# HUB.net
KiCad netlist of a schematic drawn in Altium Designer
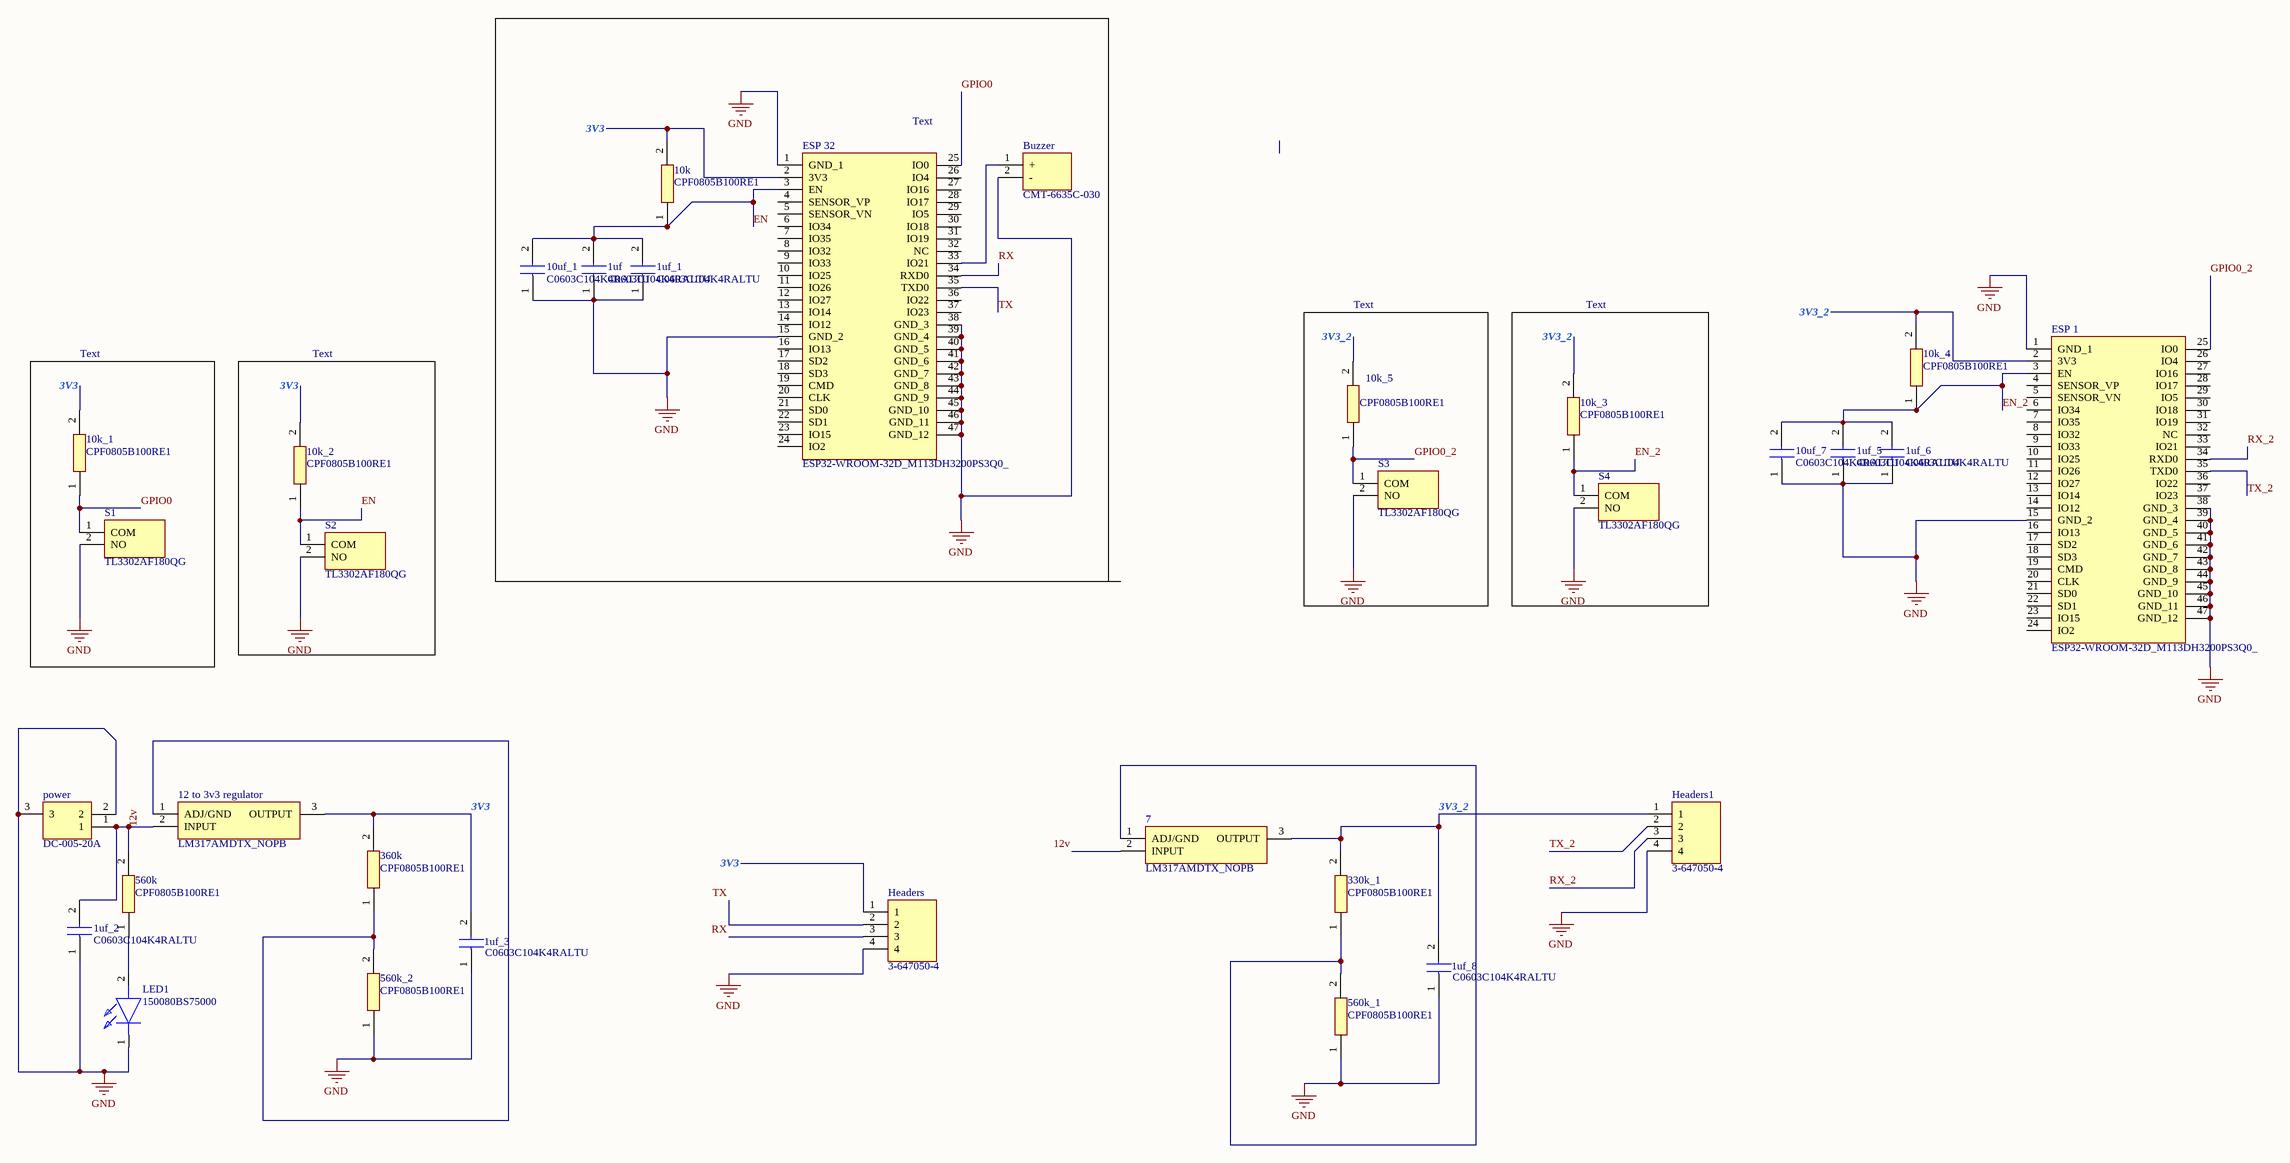
[diagram p0: HUB.SchDoc]

(export (version "E")
  (design (tool "Eeschema 10.0.6"))
  (components
    (comp (ref "1uf")
      (value "C0603C104K4RALTU")
      (footprint "SamacSys:C0603")
      (description "Capacitor")
      (fields (field (name "MOUSER PART NUMBER") "80-C0603C104K4RAL"))
      (libsource (lib "*") (part "C0603C104K4RALTU"))
    )
    (comp (ref "1uf_1")
      (value "C0603C104K4RALTU")
      (footprint "SamacSys:C0603")
      (description "Capacitor")
      (fields (field (name "MOUSER PART NUMBER") "80-C0603C104K4RAL"))
      (libsource (lib "*") (part "C0603C104K4RALTU"))
    )
    (comp (ref "1uf_2")
      (value "C0603C104K4RALTU")
      (footprint "SamacSys:C0603")
      (description "Capacitor")
      (fields (field (name "MOUSER PART NUMBER") "80-C0603C104K4RAL"))
      (libsource (lib "*") (part "C0603C104K4RALTU"))
    )
    (comp (ref "1uf_3")
      (value "C0603C104K4RALTU")
      (footprint "SamacSys:C0603")
      (description "Capacitor")
      (fields (field (name "MOUSER PART NUMBER") "80-C0603C104K4RAL"))
      (libsource (lib "*") (part "C0603C104K4RALTU"))
    )
    (comp (ref "1uf_5")
      (value "C0603C104K4RALTU")
      (footprint "SamacSys:C0603")
      (description "Capacitor")
      (fields (field (name "MOUSER PART NUMBER") "80-C0603C104K4RAL"))
      (libsource (lib "*") (part "C0603C104K4RALTU"))
    )
    (comp (ref "1uf_6")
      (value "C0603C104K4RALTU")
      (footprint "SamacSys:C0603")
      (description "Capacitor")
      (fields (field (name "MOUSER PART NUMBER") "80-C0603C104K4RAL"))
      (libsource (lib "*") (part "C0603C104K4RALTU"))
    )
    (comp (ref "1uf_8")
      (value "C0603C104K4RALTU")
      (footprint "SamacSys:C0603")
      (description "Capacitor")
      (fields (field (name "MOUSER PART NUMBER") "80-C0603C104K4RAL"))
      (libsource (lib "*") (part "C0603C104K4RALTU"))
    )
    (comp (ref "7")
      (value "LM317AMDTX_NOPB")
      (footprint "SamacSys:LM78M05CDT")
      (description "Integrated Circuit")
      (fields
        (field (name "MANUFACTURER_PART_NUMBER") "LM317AMDTX/NOPB")
        (field (name "MOUSER PART NUMBER") "926-LM317AMDTX/NOPB")
      )
      (libsource (lib "*") (part "LM317AMDTX_NOPB"))
    )
    (comp (ref "10k")
      (value "CPF0805B100RE1")
      (footprint "SamacSys:RESC2012X65N")
      (description "Resistor")
      (fields (field (name "MOUSER PART NUMBER") "279-CPF0805B100RE1"))
      (libsource (lib "*") (part "CPF0805B100RE1"))
    )
    (comp (ref "10k_1")
      (value "CPF0805B100RE1")
      (footprint "SamacSys:RESC2012X65N")
      (description "Resistor")
      (fields (field (name "MOUSER PART NUMBER") "279-CPF0805B100RE1"))
      (libsource (lib "*") (part "CPF0805B100RE1"))
    )
    (comp (ref "10k_2")
      (value "CPF0805B100RE1")
      (footprint "SamacSys:RESC2012X65N")
      (description "Resistor")
      (fields (field (name "MOUSER PART NUMBER") "279-CPF0805B100RE1"))
      (libsource (lib "*") (part "CPF0805B100RE1"))
    )
    (comp (ref "10k_3")
      (value "CPF0805B100RE1")
      (footprint "SamacSys:RESC2012X65N")
      (description "Resistor")
      (fields (field (name "MOUSER PART NUMBER") "279-CPF0805B100RE1"))
      (libsource (lib "*") (part "CPF0805B100RE1"))
    )
    (comp (ref "10k_4")
      (value "CPF0805B100RE1")
      (footprint "SamacSys:RESC2012X65N")
      (description "Resistor")
      (fields (field (name "MOUSER PART NUMBER") "279-CPF0805B100RE1"))
      (libsource (lib "*") (part "CPF0805B100RE1"))
    )
    (comp (ref "10k_5")
      (value "CPF0805B100RE1")
      (footprint "SamacSys:RESC2012X65N")
      (description "Resistor")
      (fields (field (name "MOUSER PART NUMBER") "279-CPF0805B100RE1"))
      (libsource (lib "*") (part "CPF0805B100RE1"))
    )
    (comp (ref "10uf_1")
      (value "C0603C104K4RALTU")
      (footprint "SamacSys:C0603")
      (description "Capacitor")
      (fields (field (name "MOUSER PART NUMBER") "80-C0603C104K4RAL"))
      (libsource (lib "*") (part "C0603C104K4RALTU"))
    )
    (comp (ref "10uf_7")
      (value "C0603C104K4RALTU")
      (footprint "SamacSys:C0603")
      (description "Capacitor")
      (fields (field (name "MOUSER PART NUMBER") "80-C0603C104K4RAL"))
      (libsource (lib "*") (part "C0603C104K4RALTU"))
    )
    (comp (ref "12 to 3v3 regulator")
      (value "LM317AMDTX_NOPB")
      (footprint "SamacSys:LM78M05CDT")
      (description "Integrated Circuit")
      (fields
        (field (name "MANUFACTURER_PART_NUMBER") "LM317AMDTX/NOPB")
        (field (name "MOUSER PART NUMBER") "926-LM317AMDTX/NOPB")
      )
      (libsource (lib "*") (part "LM317AMDTX_NOPB"))
    )
    (comp (ref "330k_1")
      (value "CPF0805B100RE1")
      (footprint "SamacSys:RESC2012X65N")
      (description "Resistor")
      (fields (field (name "MOUSER PART NUMBER") "279-CPF0805B100RE1"))
      (libsource (lib "*") (part "CPF0805B100RE1"))
    )
    (comp (ref "360k")
      (value "CPF0805B100RE1")
      (footprint "SamacSys:RESC2012X65N")
      (description "Resistor")
      (fields (field (name "MOUSER PART NUMBER") "279-CPF0805B100RE1"))
      (libsource (lib "*") (part "CPF0805B100RE1"))
    )
    (comp (ref "560k")
      (value "CPF0805B100RE1")
      (footprint "SamacSys:RESC2012X65N")
      (description "Resistor")
      (fields (field (name "MOUSER PART NUMBER") "279-CPF0805B100RE1"))
      (libsource (lib "*") (part "CPF0805B100RE1"))
    )
    (comp (ref "560k_1")
      (value "CPF0805B100RE1")
      (footprint "SamacSys:RESC2012X65N")
      (description "Resistor")
      (fields (field (name "MOUSER PART NUMBER") "279-CPF0805B100RE1"))
      (libsource (lib "*") (part "CPF0805B100RE1"))
    )
    (comp (ref "560k_2")
      (value "CPF0805B100RE1")
      (footprint "SamacSys:RESC2012X65N")
      (description "Resistor")
      (fields (field (name "MOUSER PART NUMBER") "279-CPF0805B100RE1"))
      (libsource (lib "*") (part "CPF0805B100RE1"))
    )
    (comp (ref "Buzzer")
      (value "CMT-6635C-030")
      (footprint "SamacSys:CMT6635C030")
      (description "Undefined or Miscellaneous")
      (fields (field (name "MOUSER PART NUMBER") "490-CMT-6635C-030"))
      (libsource (lib "*") (part "CMT-6635C-030"))
    )
    (comp (ref "ESP 1")
      (value "ESP32-WROOM-32D_M113DH3200PS3Q0_")
      (footprint "SamacSys:ESP32WROOM32DM113DH3200PS3Q0")
      (description "Integrated Circuit")
      (fields
        (field (name "MANUFACTURER_PART_NUMBER") "ESP32-WROOM-32D(M113DH3200PS3Q0)")
        (field (name "MOUSER PART NUMBER") "356-ESPWROOM3200PS3")
      )
      (libsource (lib "*") (part "ESP32-WROOM-32D_M113DH3200PS3Q0_"))
    )
    (comp (ref "ESP 32")
      (value "ESP32-WROOM-32D_M113DH3200PS3Q0_")
      (footprint "SamacSys:ESP32WROOM32DM113DH3200PS3Q0")
      (description "Integrated Circuit")
      (fields
        (field (name "MANUFACTURER_PART_NUMBER") "ESP32-WROOM-32D(M113DH3200PS3Q0)")
        (field (name "MOUSER PART NUMBER") "356-ESPWROOM3200PS3")
      )
      (libsource (lib "*") (part "ESP32-WROOM-32D_M113DH3200PS3Q0_"))
    )
    (comp (ref "Headers")
      (value "3-647050-4")
      (footprint "SamacSys:SHDR4W66P0X254_1X4_1016X635X1079P")
      (description "Connector")
      (fields (field (name "MOUSER PART NUMBER") "571-3-647050-4"))
      (libsource (lib "*") (part "3-647050-4"))
    )
    (comp (ref "Headers1")
      (value "3-647050-4")
      (footprint "SamacSys:SHDR4W66P0X254_1X4_1016X635X1079P")
      (description "Connector")
      (fields (field (name "MOUSER PART NUMBER") "571-3-647050-4"))
      (libsource (lib "*") (part "3-647050-4"))
    )
    (comp (ref "LED1")
      (value "150080BS75000")
      (footprint "SamacSys:LEDC2012X80N")
      (description "LED")
      (fields (field (name "MOUSER PART NUMBER") "710-150080BS75000"))
      (libsource (lib "*") (part "150080BS75000"))
    )
    (comp (ref "power")
      (value "DC-005-20A")
      (footprint "SamacSys:DC00520A")
      (description "Connector")
      (libsource (lib "*") (part "DC-005-20A"))
    )
    (comp (ref "S1")
      (value "TL3302AF180QG")
      (footprint "SamacSys:TL3302AF180QG")
      (description "Switch")
      (fields (field (name "MOUSER PART NUMBER") "612-TL3302A"))
      (libsource (lib "*") (part "TL3302AF180QG"))
    )
    (comp (ref "S2")
      (value "TL3302AF180QG")
      (footprint "SamacSys:TL3302AF180QG")
      (description "Switch")
      (fields (field (name "MOUSER PART NUMBER") "612-TL3302A"))
      (libsource (lib "*") (part "TL3302AF180QG"))
    )
    (comp (ref "S3")
      (value "TL3302AF180QG")
      (footprint "SamacSys:TL3302AF180QG")
      (description "Switch")
      (fields (field (name "MOUSER PART NUMBER") "612-TL3302A"))
      (libsource (lib "*") (part "TL3302AF180QG"))
    )
    (comp (ref "S4")
      (value "TL3302AF180QG")
      (footprint "SamacSys:TL3302AF180QG")
      (description "Switch")
      (fields (field (name "MOUSER PART NUMBER") "612-TL3302A"))
      (libsource (lib "*") (part "TL3302AF180QG"))
    )
  )
  (nets
    (net (code "1") (name "/3V3") (class "Default")
      (node (ref "10k") (pin "2") (pinfunction "2_2") (pintype "passive"))
      (node (ref "10k_1") (pin "2") (pinfunction "2_2") (pintype "passive"))
      (node (ref "10k_2") (pin "2") (pinfunction "2_2") (pintype "passive"))
      (node (ref "12 to 3v3 regulator") (pin "3") (pinfunction "OUTPUT_3") (pintype "passive"))
      (node (ref "1uf_3") (pin "2") (pinfunction "2_2") (pintype "passive"))
      (node (ref "360k") (pin "2") (pinfunction "2_2") (pintype "passive"))
      (node (ref "ESP 32") (pin "2") (pinfunction "3V3_2") (pintype "passive"))
      (node (ref "Headers") (pin "1") (pinfunction "1_1") (pintype "passive"))
    )
    (net (code "2") (name "/3V3_2") (class "Default")
      (node (ref "10k_3") (pin "2") (pinfunction "2_2") (pintype "passive"))
      (node (ref "10k_4") (pin "2") (pinfunction "2_2") (pintype "passive"))
      (node (ref "10k_5") (pin "2") (pinfunction "2_2") (pintype "passive"))
      (node (ref "1uf_8") (pin "2") (pinfunction "2_2") (pintype "passive"))
      (node (ref "330k_1") (pin "2") (pinfunction "2_2") (pintype "passive"))
      (node (ref "7") (pin "3") (pinfunction "OUTPUT_3") (pintype "passive"))
      (node (ref "ESP 1") (pin "2") (pinfunction "3V3_2") (pintype "passive"))
      (node (ref "Headers1") (pin "1") (pinfunction "1_1") (pintype "passive"))
    )
    (net (code "3") (name "/12v") (class "Default")
      (node (ref "12 to 3v3 regulator") (pin "2") (pinfunction "INPUT_2") (pintype "passive"))
      (node (ref "1uf_2") (pin "2") (pinfunction "2_2") (pintype "passive"))
      (node (ref "560k") (pin "2") (pinfunction "2_2") (pintype "passive"))
      (node (ref "7") (pin "2") (pinfunction "INPUT_2") (pintype "passive"))
      (node (ref "power") (pin "1") (pinfunction "1_1") (pintype "passive"))
    )
    (net (code "4") (name "/EN") (class "Default")
      (node (ref "10k") (pin "1") (pinfunction "1_1") (pintype "passive"))
      (node (ref "10k_2") (pin "1") (pinfunction "1_1") (pintype "passive"))
      (node (ref "10uf_1") (pin "2") (pinfunction "2_2") (pintype "passive"))
      (node (ref "1uf") (pin "2") (pinfunction "2_2") (pintype "passive"))
      (node (ref "1uf_1") (pin "2") (pinfunction "2_2") (pintype "passive"))
      (node (ref "ESP 32") (pin "3") (pinfunction "EN_3") (pintype "passive"))
      (node (ref "S2") (pin "1") (pinfunction "COM_1") (pintype "passive"))
    )
    (net (code "5") (name "/EN_2") (class "Default")
      (node (ref "10k_3") (pin "1") (pinfunction "1_1") (pintype "passive"))
      (node (ref "10k_4") (pin "1") (pinfunction "1_1") (pintype "passive"))
      (node (ref "10uf_7") (pin "2") (pinfunction "2_2") (pintype "passive"))
      (node (ref "1uf_5") (pin "2") (pinfunction "2_2") (pintype "passive"))
      (node (ref "1uf_6") (pin "2") (pinfunction "2_2") (pintype "passive"))
      (node (ref "ESP 1") (pin "3") (pinfunction "EN_3") (pintype "passive"))
      (node (ref "S4") (pin "1") (pinfunction "COM_1") (pintype "passive"))
    )
    (net (code "6") (name "/GPIO0") (class "Default")
      (node (ref "10k_1") (pin "1") (pinfunction "1_1") (pintype "passive"))
      (node (ref "ESP 32") (pin "25") (pinfunction "IO0_25") (pintype "passive"))
      (node (ref "S1") (pin "1") (pinfunction "COM_1") (pintype "passive"))
    )
    (net (code "7") (name "/GPIO0_2") (class "Default")
      (node (ref "10k_5") (pin "1") (pinfunction "1_1") (pintype "passive"))
      (node (ref "ESP 1") (pin "25") (pinfunction "IO0_25") (pintype "passive"))
      (node (ref "S3") (pin "1") (pinfunction "COM_1") (pintype "passive"))
    )
    (net (code "8") (name "/RX") (class "Default")
      (node (ref "ESP 32") (pin "34") (pinfunction "RXD0_34") (pintype "passive"))
      (node (ref "Headers") (pin "3") (pinfunction "3_3") (pintype "passive"))
    )
    (net (code "9") (name "/RX_2") (class "Default")
      (node (ref "ESP 1") (pin "34") (pinfunction "RXD0_34") (pintype "passive"))
      (node (ref "Headers1") (pin "3") (pinfunction "3_3") (pintype "passive"))
    )
    (net (code "10") (name "/TX") (class "Default")
      (node (ref "ESP 32") (pin "35") (pinfunction "TXD0_35") (pintype "passive"))
      (node (ref "Headers") (pin "2") (pinfunction "2_2") (pintype "passive"))
    )
    (net (code "11") (name "/TX_2") (class "Default")
      (node (ref "ESP 1") (pin "35") (pinfunction "TXD0_35") (pintype "passive"))
      (node (ref "Headers1") (pin "2") (pinfunction "2_2") (pintype "passive"))
    )
    (net (code "12") (name "GND") (class "Default")
      (node (ref "10uf_1") (pin "1") (pinfunction "1_1") (pintype "passive"))
      (node (ref "10uf_7") (pin "1") (pinfunction "1_1") (pintype "passive"))
      (node (ref "1uf") (pin "1") (pinfunction "1_1") (pintype "passive"))
      (node (ref "1uf_1") (pin "1") (pinfunction "1_1") (pintype "passive"))
      (node (ref "1uf_2") (pin "1") (pinfunction "1_1") (pintype "passive"))
      (node (ref "1uf_3") (pin "1") (pinfunction "1_1") (pintype "passive"))
      (node (ref "1uf_5") (pin "1") (pinfunction "1_1") (pintype "passive"))
      (node (ref "1uf_6") (pin "1") (pinfunction "1_1") (pintype "passive"))
      (node (ref "1uf_8") (pin "1") (pinfunction "1_1") (pintype "passive"))
      (node (ref "560k_1") (pin "1") (pinfunction "1_1") (pintype "passive"))
      (node (ref "560k_2") (pin "1") (pinfunction "1_1") (pintype "passive"))
      (node (ref "Buzzer") (pin "2") (pinfunction "-_2") (pintype "passive"))
      (node (ref "ESP 1") (pin "1") (pinfunction "GND_1_1") (pintype "passive"))
      (node (ref "ESP 1") (pin "15") (pinfunction "GND_2_15") (pintype "passive"))
      (node (ref "ESP 1") (pin "38") (pinfunction "GND_3_38") (pintype "passive"))
      (node (ref "ESP 1") (pin "39") (pinfunction "GND_4_39") (pintype "passive"))
      (node (ref "ESP 1") (pin "40") (pinfunction "GND_5_40") (pintype "passive"))
      (node (ref "ESP 1") (pin "41") (pinfunction "GND_6_41") (pintype "passive"))
      (node (ref "ESP 1") (pin "42") (pinfunction "GND_7_42") (pintype "passive"))
      (node (ref "ESP 1") (pin "43") (pinfunction "GND_8_43") (pintype "passive"))
      (node (ref "ESP 1") (pin "44") (pinfunction "GND_9_44") (pintype "passive"))
      (node (ref "ESP 1") (pin "45") (pinfunction "GND_10_45") (pintype "passive"))
      (node (ref "ESP 1") (pin "46") (pinfunction "GND_11_46") (pintype "passive"))
      (node (ref "ESP 1") (pin "47") (pinfunction "GND_12_47") (pintype "passive"))
      (node (ref "ESP 32") (pin "1") (pinfunction "GND_1_1") (pintype "passive"))
      (node (ref "ESP 32") (pin "15") (pinfunction "GND_2_15") (pintype "passive"))
      (node (ref "ESP 32") (pin "38") (pinfunction "GND_3_38") (pintype "passive"))
      (node (ref "ESP 32") (pin "39") (pinfunction "GND_4_39") (pintype "passive"))
      (node (ref "ESP 32") (pin "40") (pinfunction "GND_5_40") (pintype "passive"))
      (node (ref "ESP 32") (pin "41") (pinfunction "GND_6_41") (pintype "passive"))
      (node (ref "ESP 32") (pin "42") (pinfunction "GND_7_42") (pintype "passive"))
      (node (ref "ESP 32") (pin "43") (pinfunction "GND_8_43") (pintype "passive"))
      (node (ref "ESP 32") (pin "44") (pinfunction "GND_9_44") (pintype "passive"))
      (node (ref "ESP 32") (pin "45") (pinfunction "GND_10_45") (pintype "passive"))
      (node (ref "ESP 32") (pin "46") (pinfunction "GND_11_46") (pintype "passive"))
      (node (ref "ESP 32") (pin "47") (pinfunction "GND_12_47") (pintype "passive"))
      (node (ref "Headers") (pin "4") (pinfunction "4_4") (pintype "passive"))
      (node (ref "Headers1") (pin "4") (pinfunction "4_4") (pintype "passive"))
      (node (ref "LED1") (pin "1") (pinfunction "K_1") (pintype "passive"))
      (node (ref "S1") (pin "2") (pinfunction "NO_2") (pintype "passive"))
      (node (ref "S2") (pin "2") (pinfunction "NO_2") (pintype "passive"))
      (node (ref "S3") (pin "2") (pinfunction "NO_2") (pintype "passive"))
      (node (ref "S4") (pin "2") (pinfunction "NO_2") (pintype "passive"))
      (node (ref "power") (pin "2") (pinfunction "2_2") (pintype "passive"))
      (node (ref "power") (pin "3") (pinfunction "3_3") (pintype "passive"))
    )
    (net (code "13") (name "Net-(7-ADJ{slash}GND)") (class "Default")
      (node (ref "330k_1") (pin "1") (pinfunction "1_1") (pintype "passive"))
      (node (ref "560k_1") (pin "2") (pinfunction "2_2") (pintype "passive"))
      (node (ref "7") (pin "1") (pinfunction "ADJ/GND_1") (pintype "passive"))
    )
    (net (code "14") (name "Net-(12 to 3v3 regulator-ADJ{slash}GND)") (class "Default")
      (node (ref "12 to 3v3 regulator") (pin "1") (pinfunction "ADJ/GND_1") (pintype "passive"))
      (node (ref "360k") (pin "1") (pinfunction "1_1") (pintype "passive"))
      (node (ref "560k_2") (pin "2") (pinfunction "2_2") (pintype "passive"))
    )
    (net (code "15") (name "Net-(Buzzer-+)") (class "Default")
      (node (ref "Buzzer") (pin "1") (pinfunction "+_1") (pintype "passive"))
      (node (ref "ESP 32") (pin "33") (pinfunction "IO21_33") (pintype "passive"))
    )
    (net (code "16") (name "Net-(LED1-A)") (class "Default")
      (node (ref "560k") (pin "1") (pinfunction "1_1") (pintype "passive"))
      (node (ref "LED1") (pin "2") (pinfunction "A_2") (pintype "passive"))
    )
    (net (code "17") (name "unconnected-(ESP 1-CLK-Pad20)") (class "Default")
      (node (ref "ESP 1") (pin "20") (pinfunction "CLK_20") (pintype "passive"))
    )
    (net (code "18") (name "unconnected-(ESP 1-CMD-Pad19)") (class "Default")
      (node (ref "ESP 1") (pin "19") (pinfunction "CMD_19") (pintype "passive"))
    )
    (net (code "19") (name "unconnected-(ESP 1-IO2-Pad24)") (class "Default")
      (node (ref "ESP 1") (pin "24") (pinfunction "IO2_24") (pintype "passive"))
    )
    (net (code "20") (name "unconnected-(ESP 1-IO4-Pad26)") (class "Default")
      (node (ref "ESP 1") (pin "26") (pinfunction "IO4_26") (pintype "passive"))
    )
    (net (code "21") (name "unconnected-(ESP 1-IO5-Pad29)") (class "Default")
      (node (ref "ESP 1") (pin "29") (pinfunction "IO5_29") (pintype "passive"))
    )
    (net (code "22") (name "unconnected-(ESP 1-IO12-Pad14)") (class "Default")
      (node (ref "ESP 1") (pin "14") (pinfunction "IO12_14") (pintype "passive"))
    )
    (net (code "23") (name "unconnected-(ESP 1-IO13-Pad16)") (class "Default")
      (node (ref "ESP 1") (pin "16") (pinfunction "IO13_16") (pintype "passive"))
    )
    (net (code "24") (name "unconnected-(ESP 1-IO14-Pad13)") (class "Default")
      (node (ref "ESP 1") (pin "13") (pinfunction "IO14_13") (pintype "passive"))
    )
    (net (code "25") (name "unconnected-(ESP 1-IO15-Pad23)") (class "Default")
      (node (ref "ESP 1") (pin "23") (pinfunction "IO15_23") (pintype "passive"))
    )
    (net (code "26") (name "unconnected-(ESP 1-IO16-Pad27)") (class "Default")
      (node (ref "ESP 1") (pin "27") (pinfunction "IO16_27") (pintype "passive"))
    )
    (net (code "27") (name "unconnected-(ESP 1-IO17-Pad28)") (class "Default")
      (node (ref "ESP 1") (pin "28") (pinfunction "IO17_28") (pintype "passive"))
    )
    (net (code "28") (name "unconnected-(ESP 1-IO18-Pad30)") (class "Default")
      (node (ref "ESP 1") (pin "30") (pinfunction "IO18_30") (pintype "passive"))
    )
    (net (code "29") (name "unconnected-(ESP 1-IO19-Pad31)") (class "Default")
      (node (ref "ESP 1") (pin "31") (pinfunction "IO19_31") (pintype "passive"))
    )
    (net (code "30") (name "unconnected-(ESP 1-IO21-Pad33)") (class "Default")
      (node (ref "ESP 1") (pin "33") (pinfunction "IO21_33") (pintype "passive"))
    )
    (net (code "31") (name "unconnected-(ESP 1-IO22-Pad36)") (class "Default")
      (node (ref "ESP 1") (pin "36") (pinfunction "IO22_36") (pintype "passive"))
    )
    (net (code "32") (name "unconnected-(ESP 1-IO23-Pad37)") (class "Default")
      (node (ref "ESP 1") (pin "37") (pinfunction "IO23_37") (pintype "passive"))
    )
    (net (code "33") (name "unconnected-(ESP 1-IO25-Pad10)") (class "Default")
      (node (ref "ESP 1") (pin "10") (pinfunction "IO25_10") (pintype "passive"))
    )
    (net (code "34") (name "unconnected-(ESP 1-IO26-Pad11)") (class "Default")
      (node (ref "ESP 1") (pin "11") (pinfunction "IO26_11") (pintype "passive"))
    )
    (net (code "35") (name "unconnected-(ESP 1-IO27-Pad12)") (class "Default")
      (node (ref "ESP 1") (pin "12") (pinfunction "IO27_12") (pintype "passive"))
    )
    (net (code "36") (name "unconnected-(ESP 1-IO32-Pad8)") (class "Default")
      (node (ref "ESP 1") (pin "8") (pinfunction "IO32_8") (pintype "passive"))
    )
    (net (code "37") (name "unconnected-(ESP 1-IO33-Pad9)") (class "Default")
      (node (ref "ESP 1") (pin "9") (pinfunction "IO33_9") (pintype "passive"))
    )
    (net (code "38") (name "unconnected-(ESP 1-IO34-Pad6)") (class "Default")
      (node (ref "ESP 1") (pin "6") (pinfunction "IO34_6") (pintype "passive"))
    )
    (net (code "39") (name "unconnected-(ESP 1-IO35-Pad7)") (class "Default")
      (node (ref "ESP 1") (pin "7") (pinfunction "IO35_7") (pintype "passive"))
    )
    (net (code "40") (name "unconnected-(ESP 1-NC-Pad32)") (class "Default")
      (node (ref "ESP 1") (pin "32") (pinfunction "NC_32") (pintype "passive"))
    )
    (net (code "41") (name "unconnected-(ESP 1-SD0-Pad21)") (class "Default")
      (node (ref "ESP 1") (pin "21") (pinfunction "SD0_21") (pintype "passive"))
    )
    (net (code "42") (name "unconnected-(ESP 1-SD1-Pad22)") (class "Default")
      (node (ref "ESP 1") (pin "22") (pinfunction "SD1_22") (pintype "passive"))
    )
    (net (code "43") (name "unconnected-(ESP 1-SD2-Pad17)") (class "Default")
      (node (ref "ESP 1") (pin "17") (pinfunction "SD2_17") (pintype "passive"))
    )
    (net (code "44") (name "unconnected-(ESP 1-SD3-Pad18)") (class "Default")
      (node (ref "ESP 1") (pin "18") (pinfunction "SD3_18") (pintype "passive"))
    )
    (net (code "45") (name "unconnected-(ESP 1-SENSOR_VN-Pad5)") (class "Default")
      (node (ref "ESP 1") (pin "5") (pinfunction "SENSOR_VN_5") (pintype "passive"))
    )
    (net (code "46") (name "unconnected-(ESP 1-SENSOR_VP-Pad4)") (class "Default")
      (node (ref "ESP 1") (pin "4") (pinfunction "SENSOR_VP_4") (pintype "passive"))
    )
    (net (code "47") (name "unconnected-(ESP 32-CLK-Pad20)") (class "Default")
      (node (ref "ESP 32") (pin "20") (pinfunction "CLK_20") (pintype "passive"))
    )
    (net (code "48") (name "unconnected-(ESP 32-CMD-Pad19)") (class "Default")
      (node (ref "ESP 32") (pin "19") (pinfunction "CMD_19") (pintype "passive"))
    )
    (net (code "49") (name "unconnected-(ESP 32-IO2-Pad24)") (class "Default")
      (node (ref "ESP 32") (pin "24") (pinfunction "IO2_24") (pintype "passive"))
    )
    (net (code "50") (name "unconnected-(ESP 32-IO4-Pad26)") (class "Default")
      (node (ref "ESP 32") (pin "26") (pinfunction "IO4_26") (pintype "passive"))
    )
    (net (code "51") (name "unconnected-(ESP 32-IO5-Pad29)") (class "Default")
      (node (ref "ESP 32") (pin "29") (pinfunction "IO5_29") (pintype "passive"))
    )
    (net (code "52") (name "unconnected-(ESP 32-IO12-Pad14)") (class "Default")
      (node (ref "ESP 32") (pin "14") (pinfunction "IO12_14") (pintype "passive"))
    )
    (net (code "53") (name "unconnected-(ESP 32-IO13-Pad16)") (class "Default")
      (node (ref "ESP 32") (pin "16") (pinfunction "IO13_16") (pintype "passive"))
    )
    (net (code "54") (name "unconnected-(ESP 32-IO14-Pad13)") (class "Default")
      (node (ref "ESP 32") (pin "13") (pinfunction "IO14_13") (pintype "passive"))
    )
    (net (code "55") (name "unconnected-(ESP 32-IO15-Pad23)") (class "Default")
      (node (ref "ESP 32") (pin "23") (pinfunction "IO15_23") (pintype "passive"))
    )
    (net (code "56") (name "unconnected-(ESP 32-IO16-Pad27)") (class "Default")
      (node (ref "ESP 32") (pin "27") (pinfunction "IO16_27") (pintype "passive"))
    )
    (net (code "57") (name "unconnected-(ESP 32-IO17-Pad28)") (class "Default")
      (node (ref "ESP 32") (pin "28") (pinfunction "IO17_28") (pintype "passive"))
    )
    (net (code "58") (name "unconnected-(ESP 32-IO18-Pad30)") (class "Default")
      (node (ref "ESP 32") (pin "30") (pinfunction "IO18_30") (pintype "passive"))
    )
    (net (code "59") (name "unconnected-(ESP 32-IO19-Pad31)") (class "Default")
      (node (ref "ESP 32") (pin "31") (pinfunction "IO19_31") (pintype "passive"))
    )
    (net (code "60") (name "unconnected-(ESP 32-IO22-Pad36)") (class "Default")
      (node (ref "ESP 32") (pin "36") (pinfunction "IO22_36") (pintype "passive"))
    )
    (net (code "61") (name "unconnected-(ESP 32-IO23-Pad37)") (class "Default")
      (node (ref "ESP 32") (pin "37") (pinfunction "IO23_37") (pintype "passive"))
    )
    (net (code "62") (name "unconnected-(ESP 32-IO25-Pad10)") (class "Default")
      (node (ref "ESP 32") (pin "10") (pinfunction "IO25_10") (pintype "passive"))
    )
    (net (code "63") (name "unconnected-(ESP 32-IO26-Pad11)") (class "Default")
      (node (ref "ESP 32") (pin "11") (pinfunction "IO26_11") (pintype "passive"))
    )
    (net (code "64") (name "unconnected-(ESP 32-IO27-Pad12)") (class "Default")
      (node (ref "ESP 32") (pin "12") (pinfunction "IO27_12") (pintype "passive"))
    )
    (net (code "65") (name "unconnected-(ESP 32-IO32-Pad8)") (class "Default")
      (node (ref "ESP 32") (pin "8") (pinfunction "IO32_8") (pintype "passive"))
    )
    (net (code "66") (name "unconnected-(ESP 32-IO33-Pad9)") (class "Default")
      (node (ref "ESP 32") (pin "9") (pinfunction "IO33_9") (pintype "passive"))
    )
    (net (code "67") (name "unconnected-(ESP 32-IO34-Pad6)") (class "Default")
      (node (ref "ESP 32") (pin "6") (pinfunction "IO34_6") (pintype "passive"))
    )
    (net (code "68") (name "unconnected-(ESP 32-IO35-Pad7)") (class "Default")
      (node (ref "ESP 32") (pin "7") (pinfunction "IO35_7") (pintype "passive"))
    )
    (net (code "69") (name "unconnected-(ESP 32-NC-Pad32)") (class "Default")
      (node (ref "ESP 32") (pin "32") (pinfunction "NC_32") (pintype "passive"))
    )
    (net (code "70") (name "unconnected-(ESP 32-SD0-Pad21)") (class "Default")
      (node (ref "ESP 32") (pin "21") (pinfunction "SD0_21") (pintype "passive"))
    )
    (net (code "71") (name "unconnected-(ESP 32-SD1-Pad22)") (class "Default")
      (node (ref "ESP 32") (pin "22") (pinfunction "SD1_22") (pintype "passive"))
    )
    (net (code "72") (name "unconnected-(ESP 32-SD2-Pad17)") (class "Default")
      (node (ref "ESP 32") (pin "17") (pinfunction "SD2_17") (pintype "passive"))
    )
    (net (code "73") (name "unconnected-(ESP 32-SD3-Pad18)") (class "Default")
      (node (ref "ESP 32") (pin "18") (pinfunction "SD3_18") (pintype "passive"))
    )
    (net (code "74") (name "unconnected-(ESP 32-SENSOR_VN-Pad5)") (class "Default")
      (node (ref "ESP 32") (pin "5") (pinfunction "SENSOR_VN_5") (pintype "passive"))
    )
    (net (code "75") (name "unconnected-(ESP 32-SENSOR_VP-Pad4)") (class "Default")
      (node (ref "ESP 32") (pin "4") (pinfunction "SENSOR_VP_4") (pintype "passive"))
    )
  )
)
